# Connectors.net
KiCad netlist of a schematic drawn in Altium Designer
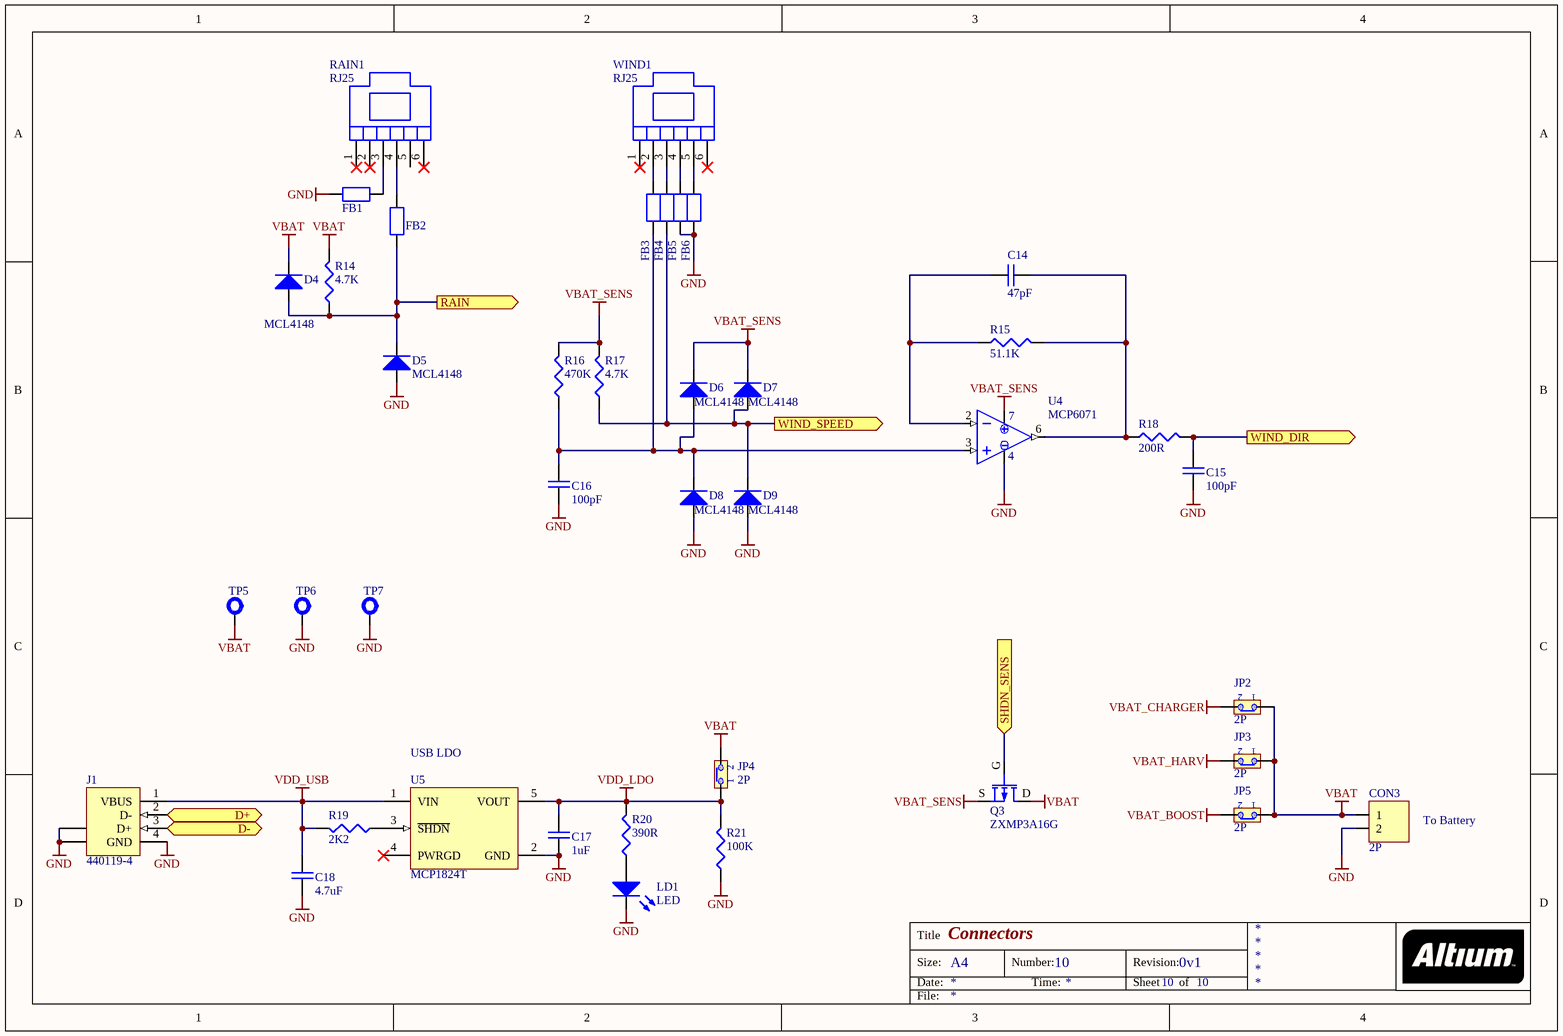
[diagram p0: Connectors.SchDoc]

(export (version "E")
  (design (tool "Eeschema 10.0.6"))
  (components
    (comp (ref "C14")
      (value "47pF")
      (footprint "0603")
      (description "Capacitor")
      (fields (field (name "OWNER") "Nuno Brum"))
      (libsource (lib "Alcetronics_Devices") (part "CAP"))
    )
    (comp (ref "C15")
      (value "100pF")
      (footprint "0603")
      (description "Capacitor")
      (fields (field (name "OWNER") "Nuno Brum"))
      (libsource (lib "Alcetronics_Devices") (part "CAP"))
    )
    (comp (ref "C16")
      (value "100pF")
      (footprint "0603")
      (description "Capacitor")
      (fields (field (name "OWNER") "Nuno Brum"))
      (libsource (lib "Alcetronics_Devices") (part "CAP"))
    )
    (comp (ref "C17")
      (value "1uF")
      (footprint "0805")
      (description "Capacitor")
      (fields (field (name "OWNER") "Nuno Brum"))
      (libsource (lib "Alcetronics_Devices") (part "CAP"))
    )
    (comp (ref "C18")
      (value "4.7uF")
      (footprint "0805")
      (description "Capacitor")
      (fields (field (name "OWNER") "Nuno Brum"))
      (libsource (lib "Alcetronics_Devices") (part "CAP"))
    )
    (comp (ref "CON3")
      (value "2P")
      (footprint "INTERLOCK2-5MM-FIXED")
      (description "Connector 2 pins")
      (fields (field (name "OWNER") "Rui Rebelo"))
      (libsource (lib "Alcetronics_EM") (part "CON02"))
    )
    (comp (ref "D4")
      (value "MCL4148")
      (footprint "0805@DIODE")
      (description "Vishay Standard Avalanche Sinterglass Diode")
      (fields (field (name "OWNER") "Nuno Brum"))
      (libsource (lib "Alcetronics_Devices") (part "Diode"))
    )
    (comp (ref "D5")
      (value "MCL4148")
      (footprint "0805@DIODE")
      (description "Vishay Standard Avalanche Sinterglass Diode")
      (fields (field (name "OWNER") "Nuno Brum"))
      (libsource (lib "Alcetronics_Devices") (part "Diode"))
    )
    (comp (ref "D6")
      (value "MCL4148")
      (footprint "0805@DIODE")
      (description "Vishay Standard Avalanche Sinterglass Diode")
      (fields (field (name "OWNER") "Nuno Brum"))
      (libsource (lib "Alcetronics_Devices") (part "Diode"))
    )
    (comp (ref "D7")
      (value "MCL4148")
      (footprint "0805@DIODE")
      (description "Vishay Standard Avalanche Sinterglass Diode")
      (fields (field (name "OWNER") "Nuno Brum"))
      (libsource (lib "Alcetronics_Devices") (part "Diode"))
    )
    (comp (ref "D8")
      (value "MCL4148")
      (footprint "0805@DIODE")
      (description "Vishay Standard Avalanche Sinterglass Diode")
      (fields (field (name "OWNER") "Nuno Brum"))
      (libsource (lib "Alcetronics_Devices") (part "Diode"))
    )
    (comp (ref "D9")
      (value "MCL4148")
      (footprint "0805@DIODE")
      (description "Vishay Standard Avalanche Sinterglass Diode")
      (fields (field (name "OWNER") "Nuno Brum"))
      (libsource (lib "Alcetronics_Devices") (part "Diode"))
    )
    (comp (ref "FB1")
      (value "150Z_100MHz")
      (footprint "1806")
      (description "Ferrite bead")
      (fields (field (name "OWNER") "Sergio Pires"))
      (libsource (lib "Alcetronics_Devices") (part "FERRITE-BEAD-AXIAL"))
    )
    (comp (ref "FB2")
      (value "150Z_100MHz")
      (footprint "1806")
      (description "Ferrite bead")
      (fields (field (name "OWNER") "Sergio Pires"))
      (libsource (lib "Alcetronics_Devices") (part "FERRITE-BEAD-AXIAL"))
    )
    (comp (ref "FB3")
      (value "150Z_100MHz")
      (footprint "1806")
      (description "Ferrite bead")
      (fields (field (name "OWNER") "Sergio Pires"))
      (libsource (lib "Alcetronics_Devices") (part "FERRITE-BEAD-AXIAL"))
    )
    (comp (ref "FB4")
      (value "150Z_100MHz")
      (footprint "1806")
      (description "Ferrite bead")
      (fields (field (name "OWNER") "Sergio Pires"))
      (libsource (lib "Alcetronics_Devices") (part "FERRITE-BEAD-AXIAL"))
    )
    (comp (ref "FB5")
      (value "150Z_100MHz")
      (footprint "1806")
      (description "Ferrite bead")
      (fields (field (name "OWNER") "Sergio Pires"))
      (libsource (lib "Alcetronics_Devices") (part "FERRITE-BEAD-AXIAL"))
    )
    (comp (ref "FB6")
      (value "150Z_100MHz")
      (footprint "1806")
      (description "Ferrite bead")
      (fields (field (name "OWNER") "Sergio Pires"))
      (libsource (lib "Alcetronics_Devices") (part "FERRITE-BEAD-AXIAL"))
    )
    (comp (ref "J1")
      (value "440119-4")
      (footprint "440119")
      (description "USB 1.1, Right Angle, Thru-Hole, B Type, Receptacle, 4 Position, Black")
      (fields (field (name "PUBLISHER") "Altium Limited"))
      (libsource (lib "Alcetronics_EM") (part "440119-4"))
    )
    (comp (ref "JP2")
      (value "2P")
      (footprint "SIP-2")
      (description "2-pin Jumper")
      (fields (field (name "OWNER") "Nuno Brum"))
      (libsource (lib "Alcetronics_EM") (part "JMP2"))
    )
    (comp (ref "JP3")
      (value "2P")
      (footprint "SIP-2")
      (description "2-pin Jumper")
      (fields (field (name "OWNER") "Nuno Brum"))
      (libsource (lib "Alcetronics_EM") (part "JMP2"))
    )
    (comp (ref "JP4")
      (value "2P")
      (footprint "SIP-2")
      (description "2-pin Jumper")
      (fields (field (name "OWNER") "Nuno Brum"))
      (libsource (lib "") (part "JMP2_1"))
    )
    (comp (ref "JP5")
      (value "2P")
      (footprint "SIP-2")
      (description "2-pin Jumper")
      (fields (field (name "OWNER") "Nuno Brum"))
      (libsource (lib "Alcetronics_EM") (part "JMP2"))
    )
    (comp (ref "LD1")
      (value "LED")
      (footprint "0805@DIODE")
      (description "Light emitting diode")
      (fields (field (name "OWNER") "Nuno Brum"))
      (libsource (lib "Alcetronics_Devices") (part "LED"))
    )
    (comp (ref "Q3")
      (value "ZXMP3A16G")
      (footprint "SOT-223@GDSD")
      (description "P-Channel Logic Level Enhancement Mode Field Effect Transistor")
      (fields (field (name "OWNER") "Nuno Brum"))
      (libsource (lib "Alcetronics_Devices") (part "MOSFET-P"))
    )
    (comp (ref "R14")
      (value "4.7K")
      (footprint "0603")
      (description "Resistor")
      (fields (field (name "OWNER") "Nuno Brum"))
      (libsource (lib "Alcetronics_Devices") (part "RES"))
    )
    (comp (ref "R15")
      (value "51.1K")
      (footprint "0603")
      (description "Resistor")
      (fields (field (name "OWNER") "Nuno Brum"))
      (libsource (lib "Alcetronics_Devices") (part "RES"))
    )
    (comp (ref "R16")
      (value "470K")
      (footprint "0603")
      (description "Resistor")
      (fields (field (name "OWNER") "Nuno Brum"))
      (libsource (lib "Alcetronics_Devices") (part "RES"))
    )
    (comp (ref "R17")
      (value "4.7K")
      (footprint "0603")
      (description "Resistor")
      (fields (field (name "OWNER") "Nuno Brum"))
      (libsource (lib "Alcetronics_Devices") (part "RES"))
    )
    (comp (ref "R18")
      (value "200R")
      (footprint "0603")
      (description "Resistor")
      (fields (field (name "OWNER") "Nuno Brum"))
      (libsource (lib "Alcetronics_Devices") (part "RES"))
    )
    (comp (ref "R19")
      (value "2K2")
      (footprint "0603")
      (description "Resistor")
      (fields (field (name "OWNER") "Nuno Brum"))
      (libsource (lib "Alcetronics_Devices") (part "RES"))
    )
    (comp (ref "R20")
      (value "390R")
      (footprint "0603")
      (description "Resistor")
      (fields (field (name "OWNER") "Nuno Brum"))
      (libsource (lib "Alcetronics_Devices") (part "RES"))
    )
    (comp (ref "R21")
      (value "100K")
      (footprint "0603")
      (description "Resistor")
      (fields (field (name "OWNER") "Nuno Brum"))
      (libsource (lib "Alcetronics_Devices") (part "RES"))
    )
    (comp (ref "RAIN1")
      (value "RJ25")
      (footprint "RJ25")
      (description "RJ25 Connector")
      (libsource (lib "Alcetronics_EM") (part "RJ25"))
    )
    (comp (ref "TP5")
      (value "Test Point")
      (footprint "TERMINAL")
      (description "Test/Probe Point")
      (fields (field (name "OWNER") "Nuno Brum"))
      (libsource (lib "Alcetronics_EM") (part "TEST-PROBE"))
    )
    (comp (ref "TP6")
      (value "Test Point")
      (footprint "TEST-PROBE2")
      (description "Test/Probe Point")
      (fields (field (name "OWNER") "Nuno Brum"))
      (libsource (lib "Alcetronics_EM") (part "TEST-PROBE"))
    )
    (comp (ref "TP7")
      (value "Test Point")
      (footprint "TERMINAL")
      (description "Test/Probe Point")
      (fields (field (name "OWNER") "Nuno Brum"))
      (libsource (lib "Alcetronics_EM") (part "TEST-PROBE"))
    )
    (comp (ref "U4")
      (value "MCP6071")
      (footprint "SOIC-8")
      (description "Low-Offset Opamp")
      (libsource (lib "Alcetronics_IC") (part "MCP6V26"))
    )
    (comp (ref "U5")
      (value "MCP1824T")
      (footprint "SOT-23-5")
      (fields (field (name "PUBLISHER") "Altium Limited"))
      (libsource (lib "Alcetronics_IC") (part "MCP1824T"))
    )
    (comp (ref "WIND1")
      (value "RJ25")
      (footprint "RJ25")
      (description "RJ25 Connector")
      (libsource (lib "Alcetronics_EM") (part "RJ25"))
    )
  )
  (nets
    (net (code "1") (name "/D+") (class "Default")
      (node (ref "J1") (pin "2") (pinfunction "D-_2") (pintype "input"))
    )
    (net (code "2") (name "/D-") (class "Default")
      (node (ref "J1") (pin "3") (pinfunction "D+_3") (pintype "input"))
    )
    (net (code "3") (name "/RAIN") (class "Default")
      (node (ref "D4") (pin "A") (pinfunction "A_A") (pintype "passive"))
      (node (ref "D5") (pin "K") (pinfunction "K_K") (pintype "passive"))
      (node (ref "FB2") (pin "1") (pinfunction "1_1") (pintype "passive"))
      (node (ref "R14") (pin "1") (pinfunction "1_1") (pintype "passive"))
    )
    (net (code "4") (name "/SHDN_SENS") (class "Default")
      (node (ref "Q3") (pin "G") (pinfunction "G_G") (pintype "passive"))
    )
    (net (code "5") (name "/WIND_DIR") (class "Default")
      (node (ref "C15") (pin "2") (pinfunction "2_2") (pintype "passive"))
      (node (ref "R18") (pin "2") (pinfunction "2_2") (pintype "passive"))
    )
    (net (code "6") (name "/WIND_SPEED") (class "Default")
      (node (ref "D7") (pin "A") (pinfunction "A_A") (pintype "passive"))
      (node (ref "D9") (pin "K") (pinfunction "K_K") (pintype "passive"))
      (node (ref "FB4") (pin "2") (pinfunction "2_2") (pintype "passive"))
      (node (ref "R17") (pin "1") (pinfunction "1_1") (pintype "passive"))
    )
    (net (code "7") (name "GND") (class "Default")
      (node (ref "C15") (pin "1") (pinfunction "1_1") (pintype "passive"))
      (node (ref "C16") (pin "1") (pinfunction "1_1") (pintype "passive"))
      (node (ref "C17") (pin "1") (pinfunction "1_1") (pintype "passive"))
      (node (ref "C18") (pin "1") (pinfunction "1_1") (pintype "passive"))
      (node (ref "CON3") (pin "2") (pinfunction "2_2") (pintype "passive"))
      (node (ref "D5") (pin "A") (pinfunction "A_A") (pintype "passive"))
      (node (ref "D8") (pin "A") (pinfunction "A_A") (pintype "passive"))
      (node (ref "D9") (pin "A") (pinfunction "A_A") (pintype "passive"))
      (node (ref "FB1") (pin "1") (pinfunction "1_1") (pintype "passive"))
      (node (ref "FB5") (pin "2") (pinfunction "2_2") (pintype "passive"))
      (node (ref "FB6") (pin "2") (pinfunction "2_2") (pintype "passive"))
      (node (ref "J1") (pin "4") (pinfunction "GND_4") (pintype "power_in"))
      (node (ref "J1") (pin "5") (pinfunction "SHLD_5") (pintype "passive"))
      (node (ref "J1") (pin "6") (pinfunction "SHLD_6") (pintype "passive"))
      (node (ref "LD1") (pin "K") (pinfunction "K_K") (pintype "passive"))
      (node (ref "R21") (pin "1") (pinfunction "1_1") (pintype "passive"))
      (node (ref "TP6") (pin "1") (pinfunction "TP_1") (pintype "passive"))
      (node (ref "TP7") (pin "1") (pinfunction "TP_1") (pintype "passive"))
      (node (ref "U4") (pin "4") (pinfunction "VSS_4") (pintype "power_in"))
      (node (ref "U5") (pin "2") (pinfunction "GND_2") (pintype "power_in"))
    )
    (net (code "8") (name "Net-(FB1-Pad2)") (class "Default")
      (node (ref "FB1") (pin "2") (pinfunction "2_2") (pintype "passive"))
      (node (ref "RAIN1") (pin "3") (pinfunction "3_3") (pintype "passive"))
    )
    (net (code "9") (name "Net-(FB2-Pad2)") (class "Default")
      (node (ref "FB2") (pin "2") (pinfunction "2_2") (pintype "passive"))
      (node (ref "RAIN1") (pin "4") (pinfunction "4_4") (pintype "passive"))
    )
    (net (code "10") (name "Net-(FB3-Pad1)") (class "Default")
      (node (ref "FB3") (pin "1") (pinfunction "1_1") (pintype "passive"))
      (node (ref "WIND1") (pin "2") (pinfunction "2_2") (pintype "passive"))
    )
    (net (code "11") (name "Net-(FB4-Pad1)") (class "Default")
      (node (ref "FB4") (pin "1") (pinfunction "1_1") (pintype "passive"))
      (node (ref "WIND1") (pin "3") (pinfunction "3_3") (pintype "passive"))
    )
    (net (code "12") (name "Net-(FB5-Pad1)") (class "Default")
      (node (ref "FB5") (pin "1") (pinfunction "1_1") (pintype "passive"))
      (node (ref "WIND1") (pin "4") (pinfunction "4_4") (pintype "passive"))
    )
    (net (code "13") (name "Net-(FB6-Pad1)") (class "Default")
      (node (ref "FB6") (pin "1") (pinfunction "1_1") (pintype "passive"))
      (node (ref "WIND1") (pin "5") (pinfunction "5_5") (pintype "passive"))
    )
    (net (code "14") (name "Net-(LD1-PadA)") (class "Default")
      (node (ref "LD1") (pin "A") (pinfunction "A_A") (pintype "passive"))
      (node (ref "R20") (pin "1") (pinfunction "1_1") (pintype "passive"))
    )
    (net (code "15") (name "Net-(U4-INN)") (class "Default")
      (node (ref "C14") (pin "1") (pinfunction "1_1") (pintype "passive"))
      (node (ref "R15") (pin "1") (pinfunction "1_1") (pintype "passive"))
      (node (ref "U4") (pin "2") (pinfunction "INN_2") (pintype "input"))
    )
    (net (code "16") (name "Net-(U4-INP)") (class "Default")
      (node (ref "C16") (pin "2") (pinfunction "2_2") (pintype "passive"))
      (node (ref "D6") (pin "A") (pinfunction "A_A") (pintype "passive"))
      (node (ref "D8") (pin "K") (pinfunction "K_K") (pintype "passive"))
      (node (ref "FB3") (pin "2") (pinfunction "2_2") (pintype "passive"))
      (node (ref "R16") (pin "1") (pinfunction "1_1") (pintype "passive"))
      (node (ref "U4") (pin "3") (pinfunction "INP_3") (pintype "input"))
    )
    (net (code "17") (name "Net-(U4-VOUT)") (class "Default")
      (node (ref "C14") (pin "2") (pinfunction "2_2") (pintype "passive"))
      (node (ref "R15") (pin "2") (pinfunction "2_2") (pintype "passive"))
      (node (ref "R18") (pin "1") (pinfunction "1_1") (pintype "passive"))
      (node (ref "U4") (pin "6") (pinfunction "VOUT_6") (pintype "output"))
    )
    (net (code "18") (name "Net-(U5-~{SHDN})") (class "Default")
      (node (ref "R19") (pin "1") (pinfunction "1_1") (pintype "passive"))
      (node (ref "U5") (pin "3") (pinfunction "~{SHDN}_3") (pintype "input"))
    )
    (net (code "19") (name "VBAT") (class "Default")
      (node (ref "CON3") (pin "1") (pinfunction "1_1") (pintype "passive"))
      (node (ref "D4") (pin "K") (pinfunction "K_K") (pintype "passive"))
      (node (ref "JP2") (pin "1") (pinfunction "1_1") (pintype "passive"))
      (node (ref "JP3") (pin "1") (pinfunction "1_1") (pintype "passive"))
      (node (ref "JP4") (pin "2") (pinfunction "2_2") (pintype "passive"))
      (node (ref "JP5") (pin "1") (pinfunction "1_1") (pintype "passive"))
      (node (ref "Q3") (pin "D") (pinfunction "D_D") (pintype "passive"))
      (node (ref "R14") (pin "2") (pinfunction "2_2") (pintype "passive"))
      (node (ref "TP5") (pin "1") (pinfunction "TP_1") (pintype "passive"))
    )
    (net (code "20") (name "VBAT_BOOST") (class "Default")
      (node (ref "JP5") (pin "2") (pinfunction "2_2") (pintype "passive"))
    )
    (net (code "21") (name "VBAT_CHARGER") (class "Default")
      (node (ref "JP2") (pin "2") (pinfunction "2_2") (pintype "passive"))
    )
    (net (code "22") (name "VBAT_HARV") (class "Default")
      (node (ref "JP3") (pin "2") (pinfunction "2_2") (pintype "passive"))
    )
    (net (code "23") (name "VBAT_SENS") (class "Default")
      (node (ref "D6") (pin "K") (pinfunction "K_K") (pintype "passive"))
      (node (ref "D7") (pin "K") (pinfunction "K_K") (pintype "passive"))
      (node (ref "Q3") (pin "S") (pinfunction "S_S") (pintype "passive"))
      (node (ref "R16") (pin "2") (pinfunction "2_2") (pintype "passive"))
      (node (ref "R17") (pin "2") (pinfunction "2_2") (pintype "passive"))
      (node (ref "U4") (pin "7") (pinfunction "VDD_7") (pintype "power_in"))
    )
    (net (code "24") (name "VDD_LDO") (class "Default")
      (node (ref "C17") (pin "2") (pinfunction "2_2") (pintype "passive"))
      (node (ref "JP4") (pin "1") (pinfunction "1_1") (pintype "passive"))
      (node (ref "R20") (pin "2") (pinfunction "2_2") (pintype "passive"))
      (node (ref "R21") (pin "2") (pinfunction "2_2") (pintype "passive"))
      (node (ref "U5") (pin "5") (pinfunction "VOUT_5") (pintype "power_in"))
    )
    (net (code "25") (name "VDD_USB") (class "Default")
      (node (ref "C18") (pin "2") (pinfunction "2_2") (pintype "passive"))
      (node (ref "J1") (pin "1") (pinfunction "VBUS_1") (pintype "power_in"))
      (node (ref "R19") (pin "2") (pinfunction "2_2") (pintype "passive"))
      (node (ref "U5") (pin "1") (pinfunction "VIN_1") (pintype "power_in"))
    )
    (net (code "26") (name "unconnected-(RAIN1-Pad1)") (class "Default")
      (node (ref "RAIN1") (pin "1") (pinfunction "1_1") (pintype "passive+no_connect"))
    )
    (net (code "27") (name "unconnected-(RAIN1-Pad2)") (class "Default")
      (node (ref "RAIN1") (pin "2") (pinfunction "2_2") (pintype "passive+no_connect"))
    )
    (net (code "28") (name "unconnected-(RAIN1-Pad5)") (class "Default")
      (node (ref "RAIN1") (pin "5") (pinfunction "5_5") (pintype "passive"))
    )
    (net (code "29") (name "unconnected-(RAIN1-Pad6)") (class "Default")
      (node (ref "RAIN1") (pin "6") (pinfunction "6_6") (pintype "passive+no_connect"))
    )
    (net (code "30") (name "unconnected-(U5-PWRGD-Pad4)") (class "Default")
      (node (ref "U5") (pin "4") (pinfunction "PWRGD_4") (pintype "power_in+no_connect"))
    )
    (net (code "31") (name "unconnected-(WIND1-Pad1)") (class "Default")
      (node (ref "WIND1") (pin "1") (pinfunction "1_1") (pintype "passive+no_connect"))
    )
    (net (code "32") (name "unconnected-(WIND1-Pad6)") (class "Default")
      (node (ref "WIND1") (pin "6") (pinfunction "6_6") (pintype "passive+no_connect"))
    )
  )
)
